# CH32H417QEU6-R0.net
KiCad netlist of a schematic drawn in Altium Designer
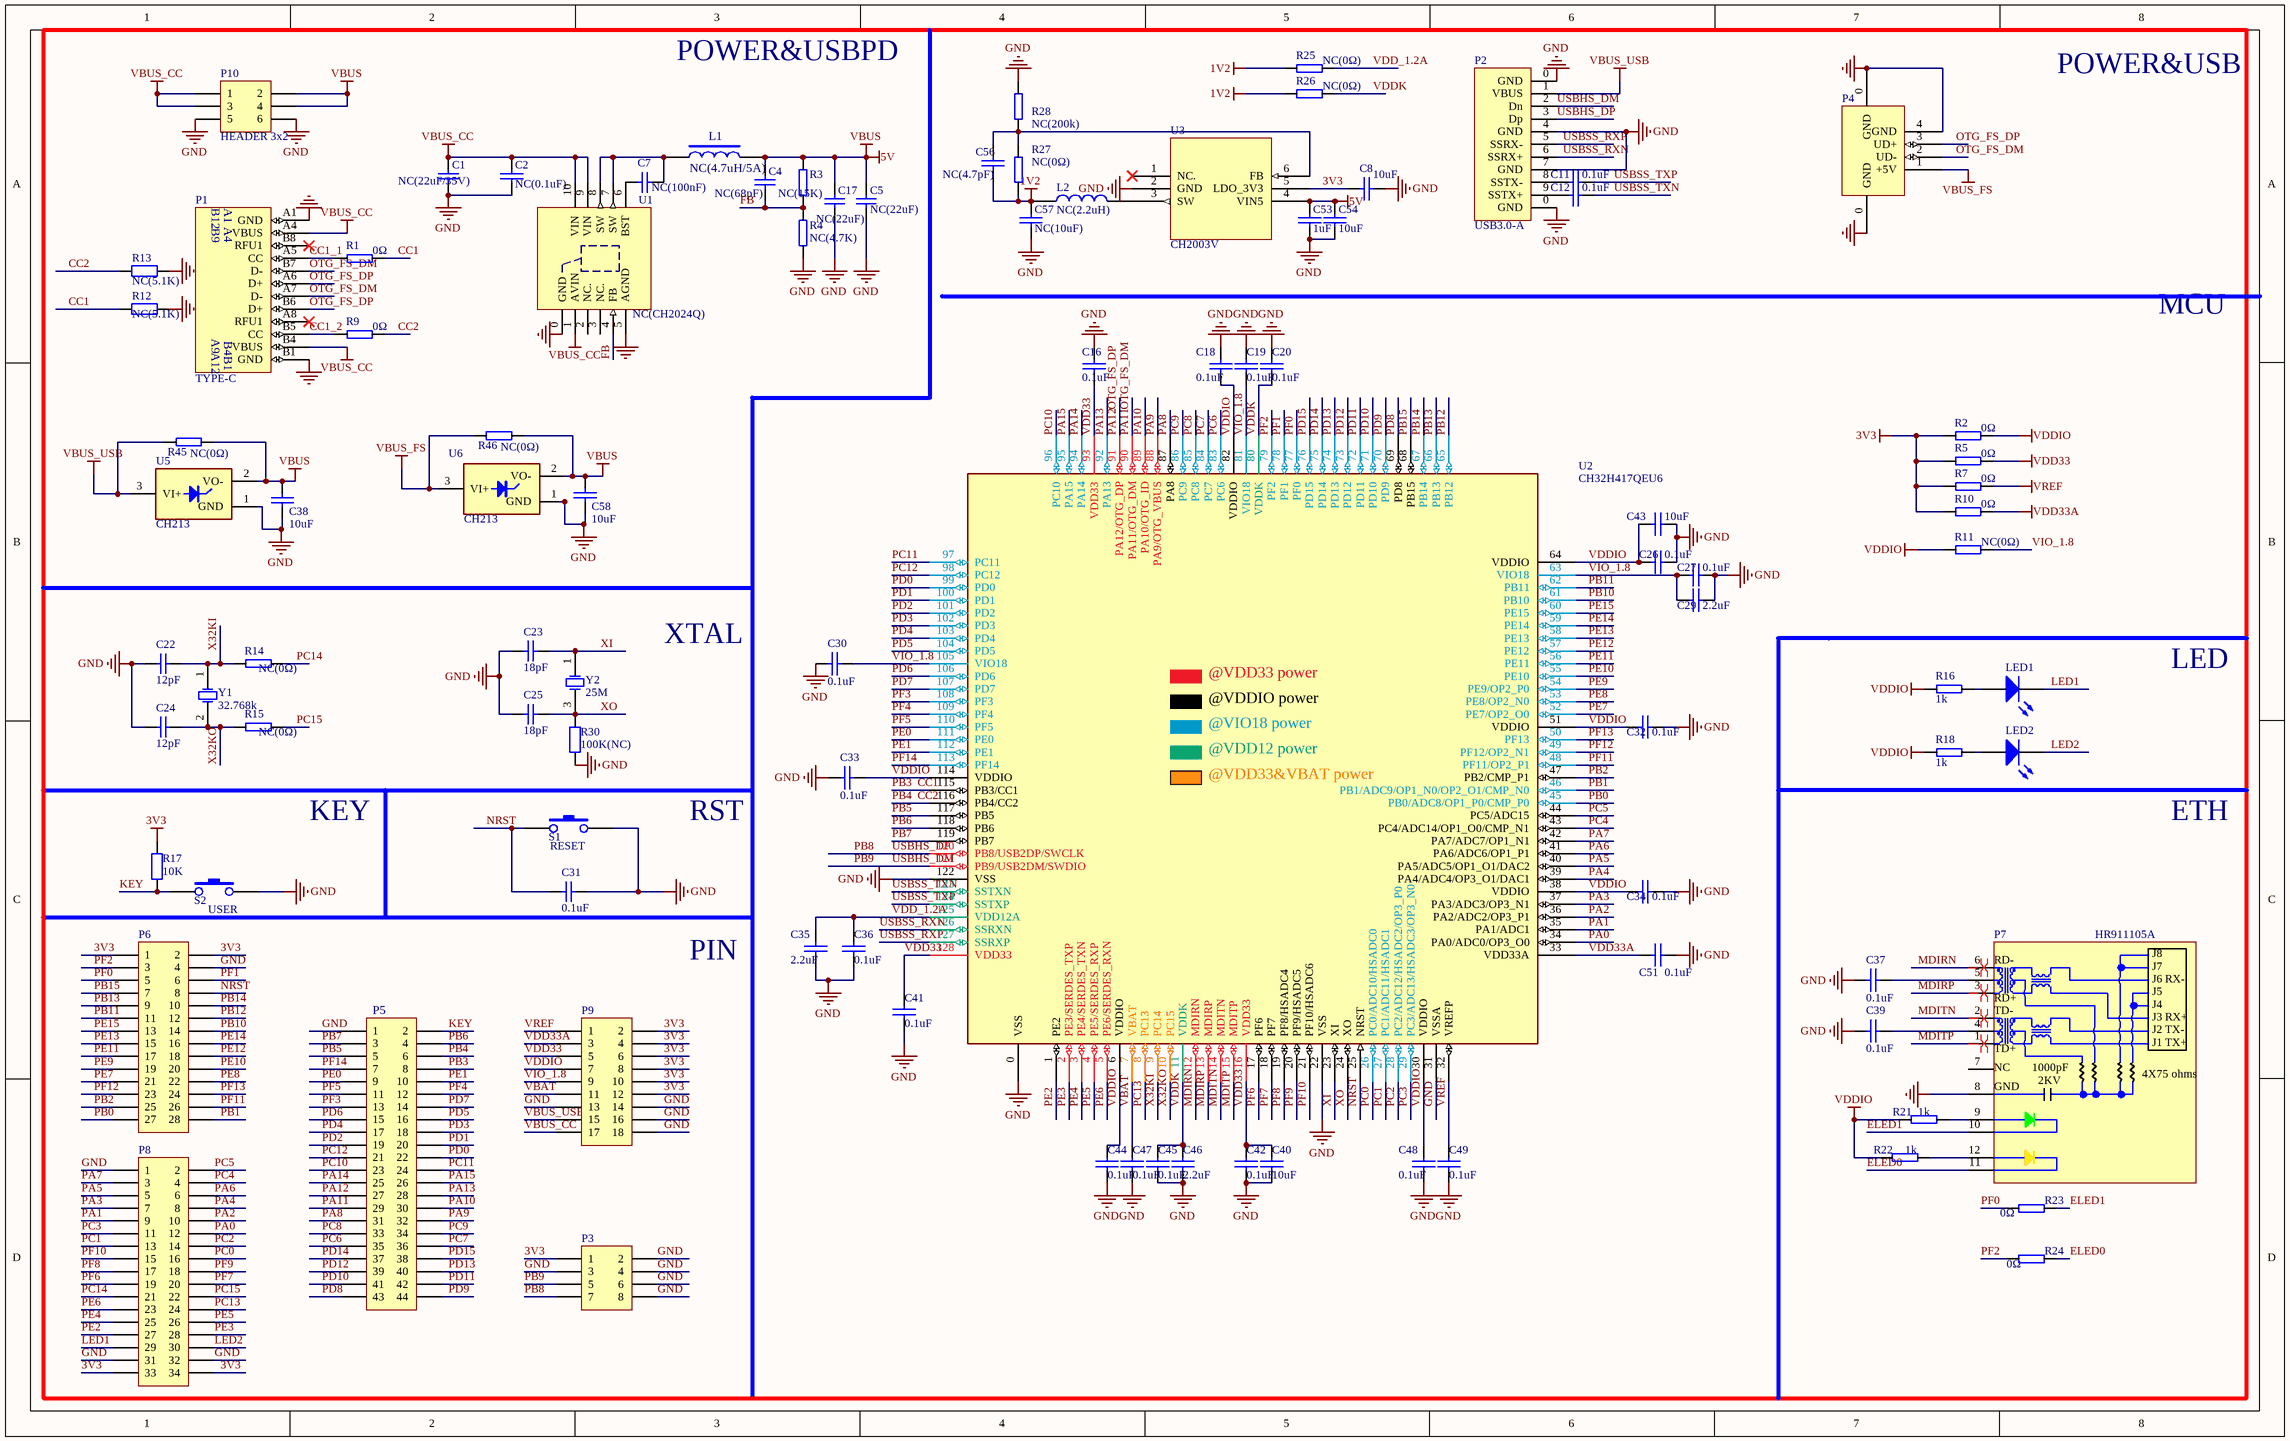
[diagram p0: CH32H417QEU6-R0.SchDoc]

(export (version "E")
  (design (tool "Eeschema 10.0.6"))
  (components
    (comp (ref "C1")
      (value "NC(22uF/35V)")
      (footprint "0805_C")
      (description "贴片电容")
      (libsource (lib "Miscellaneous Devices LC") (part "0603 100nF (104) 10% 50V"))
    )
    (comp (ref "C2")
      (value "NC(0.1uF)")
      (footprint "0402_C")
      (description "Capacitor")
      (libsource (lib "*") (part "CAP"))
    )
    (comp (ref "C4")
      (value "NC(68pF)")
      (footprint "0402_C")
      (description "贴片电容")
      (libsource (lib "Miscellaneous Devices LC") (part "0603 100nF (104) 10% 50V"))
    )
    (comp (ref "C5")
      (value "NC(22uF)")
      (footprint "0805_C")
      (description "贴片电容")
      (libsource (lib "Miscellaneous Devices LC") (part "0603 100nF (104) 10% 50V"))
    )
    (comp (ref "C7")
      (value "NC(100nF)")
      (footprint "0402_C")
      (description "贴片电容")
      (libsource (lib "Miscellaneous Devices LC") (part "0603 1uF (105) 10% 50V"))
    )
    (comp (ref "C8")
      (value "10uF")
      (footprint "0603_C")
      (description "Capacitor")
      (libsource (lib "*") (part "CAP"))
    )
    (comp (ref "C11")
      (value "0.1uF")
      (footprint "0402_C")
      (description "Capacitor")
      (libsource (lib "*") (part "CAP"))
    )
    (comp (ref "C12")
      (value "0.1uF")
      (footprint "0402_C")
      (description "Capacitor")
      (libsource (lib "*") (part "CAP"))
    )
    (comp (ref "C16")
      (value "0.1uF")
      (footprint "0402_C")
      (description "Capacitor")
      (libsource (lib "*") (part "CAP"))
    )
    (comp (ref "C17")
      (value "NC(22uF)")
      (footprint "0805_C")
      (description "贴片电容")
      (libsource (lib "Miscellaneous Devices LC") (part "0603 100nF (104) 10% 50V"))
    )
    (comp (ref "C18")
      (value "0.1uF")
      (footprint "0402_C")
      (description "Capacitor")
      (libsource (lib "*") (part "CAP"))
    )
    (comp (ref "C19")
      (value "0.1uF")
      (footprint "0402_C")
      (description "Capacitor")
      (libsource (lib "*") (part "CAP"))
    )
    (comp (ref "C20")
      (value "0.1uF")
      (footprint "0402_C")
      (description "Capacitor")
      (libsource (lib "*") (part "CAP"))
    )
    (comp (ref "C22")
      (value "12pF")
      (footprint "0402_C")
      (description "Capacitor")
      (libsource (lib "Miscellaneous Devices") (part "Cap"))
    )
    (comp (ref "C23")
      (value "18pF")
      (footprint "0402_C")
      (description "Capacitor")
      (libsource (lib "Miscellaneous Devices") (part "Cap"))
    )
    (comp (ref "C24")
      (value "12pF")
      (footprint "0402_C")
      (description "Capacitor")
      (libsource (lib "Miscellaneous Devices") (part "Cap"))
    )
    (comp (ref "C25")
      (value "18pF")
      (footprint "0402_C")
      (description "Capacitor")
      (libsource (lib "Miscellaneous Devices") (part "Cap"))
    )
    (comp (ref "C26")
      (value "0.1uF")
      (footprint "0402_C")
      (description "Capacitor")
      (libsource (lib "*") (part "CAP"))
    )
    (comp (ref "C27")
      (value "0.1uF")
      (footprint "0402_C")
      (description "Capacitor")
      (libsource (lib "*") (part "CAP"))
    )
    (comp (ref "C29")
      (value "2.2uF")
      (footprint "0402_C")
      (description "Capacitor")
      (libsource (lib "*") (part "CAP"))
    )
    (comp (ref "C30")
      (value "0.1uF")
      (footprint "0402_C")
      (description "Capacitor")
      (libsource (lib "*") (part "CAP"))
    )
    (comp (ref "C31")
      (value "0.1uF")
      (footprint "0402_C")
      (description "Capacitor")
      (libsource (lib "Miscellaneous Devices") (part "Cap"))
    )
    (comp (ref "C32")
      (value "0.1uF")
      (footprint "0402_C")
      (description "Capacitor")
      (libsource (lib "*") (part "CAP"))
    )
    (comp (ref "C33")
      (value "0.1uF")
      (footprint "0402_C")
      (description "Capacitor")
      (libsource (lib "*") (part "CAP"))
    )
    (comp (ref "C34")
      (value "0.1uF")
      (footprint "0402_C")
      (description "Capacitor")
      (libsource (lib "*") (part "CAP"))
    )
    (comp (ref "C35")
      (value "2.2uF")
      (footprint "0402_C")
      (description "Capacitor")
      (libsource (lib "*") (part "CAP"))
    )
    (comp (ref "C36")
      (value "0.1uF")
      (footprint "0402_C")
      (description "Capacitor")
      (libsource (lib "*") (part "CAP"))
    )
    (comp (ref "C37")
      (value "0.1uF")
      (footprint "0402_C")
      (description "Capacitor")
      (libsource (lib "wch_sch_others") (part "CAP"))
    )
    (comp (ref "C38")
      (value "10uF")
      (footprint "0603_C")
      (description "Capacitor")
      (libsource (lib "") (part "CAP_1"))
    )
    (comp (ref "C39")
      (value "0.1uF")
      (footprint "0402_C")
      (description "Capacitor")
      (libsource (lib "wch_sch_others") (part "CAP"))
    )
    (comp (ref "C40")
      (value "10uF")
      (footprint "0603_C")
      (description "Capacitor")
      (libsource (lib "*") (part "CAP"))
    )
    (comp (ref "C41")
      (value "0.1uF")
      (footprint "0402_C")
      (description "Capacitor")
      (libsource (lib "*") (part "CAP"))
    )
    (comp (ref "C42")
      (value "0.1uF")
      (footprint "0402_C")
      (description "Capacitor")
      (libsource (lib "*") (part "CAP"))
    )
    (comp (ref "C43")
      (value "10uF")
      (footprint "0603_C")
      (description "Capacitor")
      (libsource (lib "*") (part "CAP"))
    )
    (comp (ref "C44")
      (value "0.1uF")
      (footprint "0402_C")
      (description "Capacitor")
      (libsource (lib "*") (part "CAP"))
    )
    (comp (ref "C45")
      (value "0.1uF")
      (footprint "0402_C")
      (description "Capacitor")
      (libsource (lib "*") (part "CAP"))
    )
    (comp (ref "C46")
      (value "2.2uF")
      (footprint "0402_C")
      (description "Capacitor")
      (libsource (lib "*") (part "CAP"))
    )
    (comp (ref "C47")
      (value "0.1uF")
      (footprint "0402_C")
      (description "Capacitor")
      (libsource (lib "*") (part "CAP"))
    )
    (comp (ref "C48")
      (value "0.1uF")
      (footprint "0402_C")
      (description "Capacitor")
      (libsource (lib "*") (part "CAP"))
    )
    (comp (ref "C49")
      (value "0.1uF")
      (footprint "0402_C")
      (description "Capacitor")
      (libsource (lib "*") (part "CAP"))
    )
    (comp (ref "C51")
      (value "0.1uF")
      (footprint "0402_C")
      (description "Capacitor")
      (libsource (lib "*") (part "CAP"))
    )
    (comp (ref "C53")
      (value "1uF")
      (footprint "0402_C")
      (description "Capacitor")
      (libsource (lib "") (part "CAP_2"))
    )
    (comp (ref "C54")
      (value "10uF")
      (footprint "0603_C")
      (description "Capacitor")
      (libsource (lib "*") (part "CAP"))
    )
    (comp (ref "C56")
      (value "NC(4.7pF)")
      (footprint "0402_C")
      (description "Capacitor")
      (libsource (lib "") (part "CAP_2"))
    )
    (comp (ref "C57")
      (value "NC(10uF)")
      (footprint "0603_C")
      (description "Capacitor")
      (libsource (lib "*") (part "CAP"))
    )
    (comp (ref "C58")
      (value "10uF")
      (footprint "0603_C")
      (description "Capacitor")
      (libsource (lib "") (part "CAP_1"))
    )
    (comp (ref "L1")
      (value "NC(4.7uH/5A)")
      (footprint "IND-SMD_L7.0-W6.6")
      (libsource (lib "wch_sch_others") (part "INDUCTOR"))
    )
    (comp (ref "L2") (value "NC(2.2uH)") (footprint "CD32") (libsource (lib "*") (part "INDUCTOR")))
    (comp (ref "LED1")
      (value "LED2  blue")
      (footprint "0603+")
      (description "Typical INFRARED GaAs LED")
      (fields (field (name "PUBLISHER") "Altium Limited"))
      (libsource (lib "Miscellaneous Devices") (part "LED0"))
    )
    (comp (ref "LED2")
      (value "LED1   blue")
      (footprint "0603+")
      (description "Typical INFRARED GaAs LED")
      (fields (field (name "PUBLISHER") "Altium Limited"))
      (libsource (lib "Miscellaneous Devices") (part "LED0"))
    )
    (comp (ref "P1")
      (value "TYPE-C")
      (footprint "TYPE-C-Receptacle-2.0")
      (libsource (lib "*") (part "TYPE-C1"))
    )
    (comp (ref "P2")
      (value "USB3.0-A")
      (footprint "USB3.0-A-Receptacle")
      (libsource (lib "wch_sch_others") (part "USB3.0-A"))
    )
    (comp (ref "P3")
      (value "HEADER 4x2")
      (footprint "MYPCB:IDC8-2.54mm")
      (description "Header, 4-Pin, Dual row")
      (libsource (lib "wch_sch_others") (part "HEADER 4x2"))
    )
    (comp (ref "P4")
      (value "USB_A")
      (footprint "USBAF")
      (description "USB Port")
      (libsource (lib "*") (part "USB"))
    )
    (comp (ref "P5")
      (value "~")
      (footprint "MYPCB:IDC44-2.54MM")
      (description "Header, 22-Pin, Dual row")
      (libsource (lib "wch_sch_others") (part "HEADER 22x2"))
    )
    (comp (ref "P6")
      (value "HEADER 14x2")
      (footprint "MYPCB:IDC28-2.54MM")
      (description "Header, 14-Pin, Dual row")
      (libsource (lib "wch_sch_others") (part "HEADER 14x2"))
    )
    (comp (ref "P7") (value "HR911105A") (footprint "HR911105A") (libsource (lib "*") (part "HR911105A")))
    (comp (ref "P8")
      (value "HEADER 17x2")
      (footprint "MYPCB:IDC34-2.54MM")
      (description "Header, 17-Pin, Dual row")
      (libsource (lib "wch_sch_others") (part "HEADER 17x2"))
    )
    (comp (ref "P9")
      (value "HEADER 9x2")
      (footprint "MYPCB:IDC18-2.54MM")
      (description "Header, 9-Pin, Dual row")
      (libsource (lib "wch_sch_others") (part "HEADER 9x2"))
    )
    (comp (ref "P10")
      (value "HEADER 3x2")
      (footprint "MYPCB:IDC6-2.54mm")
      (description "Header, 3-Pin, Dual row")
      (libsource (lib "wch_sch_others") (part "HEADER 3x2"))
    )
    (comp (ref "R1") (value "0Ω") (footprint "0402") (libsource (lib "wch_sch_others") (part "RES")))
    (comp (ref "R2") (value "0Ω") (footprint "0402") (libsource (lib "wch_sch_others") (part "RES")))
    (comp (ref "R3") (value "NC(15K)") (footprint "0402") (libsource (lib "wch_sch_others(1)") (part "RES")))
    (comp (ref "R4") (value "NC(4.7K)") (footprint "0402") (libsource (lib "wch_sch_others(1)") (part "RES")))
    (comp (ref "R5") (value "0Ω") (footprint "0402") (libsource (lib "wch_sch_others") (part "RES")))
    (comp (ref "R7") (value "0Ω") (footprint "0402") (libsource (lib "wch_sch_others") (part "RES")))
    (comp (ref "R9") (value "0Ω") (footprint "0402") (libsource (lib "wch_sch_others") (part "RES")))
    (comp (ref "R10") (value "0Ω") (footprint "0402") (libsource (lib "wch_sch_others") (part "RES")))
    (comp (ref "R11") (value "NC(0Ω)") (footprint "0402") (libsource (lib "wch_sch_others") (part "RES")))
    (comp (ref "R12")
      (value "NC(5.1K)")
      (footprint "0402")
      (description "Resistor")
      (libsource (lib "Miscellaneous Devices") (part "Res2"))
    )
    (comp (ref "R13")
      (value "NC(5.1K)")
      (footprint "0402")
      (description "Resistor")
      (libsource (lib "Miscellaneous Devices") (part "Res2"))
    )
    (comp (ref "R14") (value "NC(0Ω)") (footprint "0402") (libsource (lib "wch_sch_others") (part "RES")))
    (comp (ref "R15") (value "NC(0Ω)") (footprint "0402") (libsource (lib "wch_sch_others") (part "RES")))
    (comp (ref "R16") (value "1k") (footprint "0402") (libsource (lib "wch_sch_others") (part "RES")))
    (comp (ref "R17")
      (value "10K")
      (footprint "0402")
      (description "Resistor")
      (libsource (lib "") (part "Res2_1"))
    )
    (comp (ref "R18") (value "1k") (footprint "0402") (libsource (lib "wch_sch_others") (part "RES")))
    (comp (ref "R21") (value "1k") (footprint "0402") (libsource (lib "") (part "RES_1")))
    (comp (ref "R22") (value "1k") (footprint "0402") (libsource (lib "") (part "RES_1")))
    (comp (ref "R23") (value "0Ω") (footprint "0402") (libsource (lib "") (part "RES_1")))
    (comp (ref "R24") (value "0Ω") (footprint "0402") (libsource (lib "") (part "RES_1")))
    (comp (ref "R25") (value "NC(0Ω)") (footprint "0402") (libsource (lib "wch_sch_others") (part "RES")))
    (comp (ref "R26") (value "NC(0Ω)") (footprint "0402") (libsource (lib "wch_sch_others") (part "RES")))
    (comp (ref "R27") (value "NC(0Ω)") (footprint "0402") (libsource (lib "wch_sch_others") (part "RES")))
    (comp (ref "R28") (value "NC(200k)") (footprint "0402") (libsource (lib "wch_sch_others") (part "RES")))
    (comp (ref "R30")
      (value "100K(NC)")
      (footprint "0402")
      (description "Resistor")
      (libsource (lib "") (part "Res2_2"))
    )
    (comp (ref "R45") (value "NC(0Ω)") (footprint "0402") (libsource (lib "") (part "RES_1")))
    (comp (ref "R46") (value "NC(0Ω)") (footprint "0402") (libsource (lib "") (part "RES_1")))
    (comp (ref "S1")
      (value "RESET")
      (footprint "SMD_6.1x3.65x2.5mm-KEY")
      (libsource (lib "wch_sch_others") (part "KEY1"))
    )
    (comp (ref "S2")
      (value "USER")
      (footprint "SMD_6.1x3.65x2.5mm-KEY")
      (libsource (lib "wch_sch_others") (part "KEY1"))
    )
    (comp (ref "U1")
      (value "NC(CH2024Q)")
      (footprint "DFN10_3X3")
      (description "Step-Down DC-DC Converter, 28V input, FB 1.2V, 3A output")
      (libsource (lib "DHXXXSCH") (part "CH2024Q"))
    )
    (comp (ref "U2")
      (value "CH32H417QEU6")
      (footprint "QFN128_12.3X12.3")
      (description "RISC-V FPU HD-MCU, 384MHz, USB3.0 & PD, 100M Ethernet, DVP, SDMMC, QSPI, OPA, ADC, DAC")
      (libsource (lib "DHXXXSCH") (part "CH32H417QET6"))
    )
    (comp (ref "U3")
      (value "CH2003V")
      (footprint "SOT-23-6")
      (description "Step-Down DC-DC Converter, 5V input, FB 0.6V, 800mA output, with LDO 3.3V * 200mA")
      (libsource (lib "DHXXXSCH") (part "CH2003K"))
    )
    (comp (ref "U5")
      (value "CH213")
      (footprint "SOT-23-3")
      (description "Ideal Diode 5V*1A")
      (libsource (lib "CHXXX") (part "CH213E"))
    )
    (comp (ref "U6")
      (value "CH213")
      (footprint "SOT-23-3")
      (description "Ideal Diode 5V*1A")
      (libsource (lib "CHXXX") (part "CH213E"))
    )
    (comp (ref "Y1")
      (value "32.768k")
      (footprint "FC-135")
      (description "Crystal Oscillator")
      (fields (field (name "PUBLISHER") "Altium Limited"))
      (libsource (lib "") (part "XTAL_1"))
    )
    (comp (ref "Y2")
      (value "25M")
      (footprint "XT3225")
      (description "Crystal Oscillator")
      (fields (field (name "PUBLISHER") "Altium Limited"))
      (libsource (lib "Miscellaneous Devices") (part "XTAL"))
    )
  )
  (nets
    (net (code "2") (name "/CC1") (class "Default")
      (node (ref "P5") (pin "8") (pinfunction "8_8") (pintype "passive"))
      (node (ref "R1") (pin "1") (pintype "passive"))
      (node (ref "R12") (pin "1") (pinfunction "1_1") (pintype "passive"))
      (node (ref "U2") (pin "115") (pinfunction "PB3/CC1_115") (pintype "bidirectional"))
    )
    (net (code "3") (name "/CC1_1") (class "Default")
      (node (ref "P1") (pin "A5") (pinfunction "CC_A5") (pintype "bidirectional"))
      (node (ref "R1") (pin "2") (pintype "passive"))
    )
    (net (code "4") (name "/CC1_2") (class "Default")
      (node (ref "P1") (pin "B5") (pinfunction "CC_B5") (pintype "bidirectional"))
      (node (ref "R9") (pin "2") (pintype "passive"))
    )
    (net (code "5") (name "/CC2") (class "Default")
      (node (ref "P5") (pin "6") (pinfunction "6_6") (pintype "passive"))
      (node (ref "R13") (pin "1") (pinfunction "1_1") (pintype "passive"))
      (node (ref "R9") (pin "1") (pintype "passive"))
      (node (ref "U2") (pin "116") (pinfunction "PB4/CC2_116") (pintype "bidirectional"))
    )
    (net (code "6") (name "/ELED0") (class "Default")
      (node (ref "P7") (pin "11") (pintype "passive"))
      (node (ref "R24") (pin "2") (pintype "passive"))
    )
    (net (code "7") (name "/ELED1") (class "Default")
      (node (ref "P7") (pin "10") (pintype "passive"))
      (node (ref "R23") (pin "2") (pintype "passive"))
    )
    (net (code "8") (name "/FB") (class "Default")
      (node (ref "C4") (pin "2") (pinfunction "2_2") (pintype "passive"))
      (node (ref "R3") (pin "1") (pintype "passive"))
      (node (ref "R4") (pin "2") (pintype "passive"))
      (node (ref "U1") (pin "4") (pinfunction "FB_4") (pintype "input"))
    )
    (net (code "9") (name "/KEY") (class "Default")
      (node (ref "P5") (pin "2") (pinfunction "2_2") (pintype "passive"))
      (node (ref "R17") (pin "2") (pinfunction "2_2") (pintype "passive"))
      (node (ref "S2") (pin "1") (pinfunction "1_1") (pintype "passive"))
    )
    (net (code "10") (name "/LED1") (class "Default")
      (node (ref "LED1") (pin "2") (pinfunction "K_2") (pintype "passive"))
      (node (ref "P8") (pin "29") (pinfunction "29_29") (pintype "passive"))
    )
    (net (code "11") (name "/LED2") (class "Default")
      (node (ref "LED2") (pin "2") (pinfunction "K_2") (pintype "passive"))
      (node (ref "P8") (pin "30") (pinfunction "30_30") (pintype "passive"))
    )
    (net (code "12") (name "/MDIRN") (class "Default")
      (node (ref "P7") (pin "6") (pintype "passive"))
      (node (ref "U2") (pin "12") (pinfunction "MDIRN_12") (pintype "bidirectional"))
    )
    (net (code "13") (name "/MDIRP") (class "Default")
      (node (ref "P7") (pin "3") (pintype "passive"))
      (node (ref "U2") (pin "13") (pinfunction "MDIRP_13") (pintype "bidirectional"))
    )
    (net (code "14") (name "/MDITN") (class "Default")
      (node (ref "P7") (pin "2") (pintype "passive"))
      (node (ref "U2") (pin "14") (pinfunction "MDITN_14") (pintype "bidirectional"))
    )
    (net (code "15") (name "/MDITP") (class "Default")
      (node (ref "P7") (pin "1") (pintype "passive"))
      (node (ref "U2") (pin "15") (pinfunction "MDITP_15") (pintype "bidirectional"))
    )
    (net (code "16") (name "/NRST") (class "Default")
      (node (ref "C31") (pin "2") (pinfunction "2_2") (pintype "passive"))
      (node (ref "P6") (pin "8") (pinfunction "8_8") (pintype "passive"))
      (node (ref "S1") (pin "1") (pinfunction "1_1") (pintype "passive"))
      (node (ref "U2") (pin "25") (pinfunction "NRST_25") (pintype "input"))
    )
    (net (code "17") (name "/OTG_FS_DM") (class "Default")
      (node (ref "P1") (pin "A7") (pinfunction "D-_A7") (pintype "bidirectional"))
      (node (ref "P1") (pin "B7") (pinfunction "D-_B7") (pintype "bidirectional"))
      (node (ref "P4") (pin "2") (pinfunction "UD-_2") (pintype "bidirectional"))
      (node (ref "P5") (pin "29") (pinfunction "29_29") (pintype "passive"))
      (node (ref "U2") (pin "90") (pinfunction "PA11/OTG_DM_90") (pintype "bidirectional"))
    )
    (net (code "18") (name "/OTG_FS_DP") (class "Default")
      (node (ref "P1") (pin "A6") (pinfunction "D+_A6") (pintype "bidirectional"))
      (node (ref "P1") (pin "B6") (pinfunction "D+_B6") (pintype "bidirectional"))
      (node (ref "P4") (pin "3") (pinfunction "UD+_3") (pintype "bidirectional"))
      (node (ref "P5") (pin "27") (pinfunction "27_27") (pintype "passive"))
      (node (ref "U2") (pin "91") (pinfunction "PA12/OTG_DP_91") (pintype "bidirectional"))
    )
    (net (code "19") (name "/PA0") (class "Default")
      (node (ref "P8") (pin "12") (pinfunction "12_12") (pintype "passive"))
      (node (ref "U2") (pin "34") (pinfunction "PA0/ADC0/OP3_O0_34") (pintype "bidirectional"))
    )
    (net (code "20") (name "/PA1") (class "Default")
      (node (ref "P8") (pin "9") (pinfunction "9_9") (pintype "passive"))
      (node (ref "U2") (pin "35") (pinfunction "PA1/ADC1_35") (pintype "bidirectional"))
    )
    (net (code "21") (name "/PA2") (class "Default")
      (node (ref "P8") (pin "10") (pinfunction "10_10") (pintype "passive"))
      (node (ref "U2") (pin "36") (pinfunction "PA2/ADC2/OP3_P1_36") (pintype "bidirectional"))
    )
    (net (code "22") (name "/PA3") (class "Default")
      (node (ref "P8") (pin "7") (pinfunction "7_7") (pintype "passive"))
      (node (ref "U2") (pin "37") (pinfunction "PA3/ADC3/OP3_N1_37") (pintype "bidirectional"))
    )
    (net (code "23") (name "/PA4") (class "Default")
      (node (ref "P8") (pin "8") (pinfunction "8_8") (pintype "passive"))
      (node (ref "U2") (pin "39") (pinfunction "PA4/ADC4/OP3_O1/DAC1_39") (pintype "bidirectional"))
    )
    (net (code "24") (name "/PA5") (class "Default")
      (node (ref "P8") (pin "5") (pinfunction "5_5") (pintype "passive"))
      (node (ref "U2") (pin "40") (pinfunction "PA5/ADC5/OP1_O1/DAC2_40") (pintype "bidirectional"))
    )
    (net (code "25") (name "/PA6") (class "Default")
      (node (ref "P8") (pin "6") (pinfunction "6_6") (pintype "passive"))
      (node (ref "U2") (pin "41") (pinfunction "PA6/ADC6/OP1_P1_41") (pintype "bidirectional"))
    )
    (net (code "26") (name "/PA7") (class "Default")
      (node (ref "P8") (pin "3") (pinfunction "3_3") (pintype "passive"))
      (node (ref "U2") (pin "42") (pinfunction "PA7/ADC7/OP1_N1_42") (pintype "bidirectional"))
    )
    (net (code "27") (name "/PA8") (class "Default")
      (node (ref "P5") (pin "31") (pinfunction "31_31") (pintype "passive"))
      (node (ref "U2") (pin "87") (pinfunction "PA8_87") (pintype "bidirectional"))
    )
    (net (code "28") (name "/PA9") (class "Default")
      (node (ref "P5") (pin "32") (pinfunction "32_32") (pintype "passive"))
      (node (ref "U2") (pin "88") (pinfunction "PA9/OTG_VBUS_88") (pintype "bidirectional"))
    )
    (net (code "29") (name "/PA10") (class "Default")
      (node (ref "P5") (pin "30") (pinfunction "30_30") (pintype "passive"))
      (node (ref "U2") (pin "89") (pinfunction "PA10/OTG_ID_89") (pintype "bidirectional"))
    )
    (net (code "30") (name "/PA13") (class "Default")
      (node (ref "P5") (pin "28") (pinfunction "28_28") (pintype "passive"))
      (node (ref "U2") (pin "92") (pinfunction "PA13_92") (pintype "bidirectional"))
    )
    (net (code "31") (name "/PA14") (class "Default")
      (node (ref "P5") (pin "25") (pinfunction "25_25") (pintype "passive"))
      (node (ref "U2") (pin "94") (pinfunction "PA14_94") (pintype "bidirectional"))
    )
    (net (code "32") (name "/PA15") (class "Default")
      (node (ref "P5") (pin "26") (pinfunction "26_26") (pintype "passive"))
      (node (ref "U2") (pin "95") (pinfunction "PA15_95") (pintype "bidirectional"))
    )
    (net (code "33") (name "/PB0") (class "Default")
      (node (ref "P6") (pin "27") (pinfunction "27_27") (pintype "passive"))
      (node (ref "U2") (pin "45") (pinfunction "PB0/ADC8/OP1_P0/CMP_P0_45") (pintype "bidirectional"))
    )
    (net (code "34") (name "/PB1") (class "Default")
      (node (ref "P6") (pin "28") (pinfunction "28_28") (pintype "passive"))
      (node (ref "U2") (pin "46") (pinfunction "PB1/ADC9/OP1_N0/OP2_O1/CMP_N0_46") (pintype "bidirectional"))
    )
    (net (code "35") (name "/PB2") (class "Default")
      (node (ref "P6") (pin "25") (pinfunction "25_25") (pintype "passive"))
      (node (ref "U2") (pin "47") (pinfunction "PB2/CMP_P1_47") (pintype "bidirectional"))
    )
    (net (code "36") (name "/PB5") (class "Default")
      (node (ref "P5") (pin "5") (pinfunction "5_5") (pintype "passive"))
      (node (ref "U2") (pin "117") (pinfunction "PB5_117") (pintype "bidirectional"))
    )
    (net (code "37") (name "/PB6") (class "Default")
      (node (ref "P5") (pin "4") (pinfunction "4_4") (pintype "passive"))
      (node (ref "U2") (pin "118") (pinfunction "PB6_118") (pintype "bidirectional"))
    )
    (net (code "38") (name "/PB7") (class "Default")
      (node (ref "P5") (pin "3") (pinfunction "3_3") (pintype "passive"))
      (node (ref "U2") (pin "119") (pinfunction "PB7_119") (pintype "bidirectional"))
    )
    (net (code "39") (name "/PB8") (class "Default")
      (node (ref "P2") (pin "3") (pinfunction "Dp_3") (pintype "passive"))
      (node (ref "P3") (pin "7") (pinfunction "7_7") (pintype "passive"))
      (node (ref "U2") (pin "120") (pinfunction "PB8/USB2DP/SWCLK_120") (pintype "bidirectional"))
    )
    (net (code "40") (name "/PB9") (class "Default")
      (node (ref "P2") (pin "2") (pinfunction "Dn_2") (pintype "passive"))
      (node (ref "P3") (pin "5") (pinfunction "5_5") (pintype "passive"))
      (node (ref "U2") (pin "121") (pinfunction "PB9/USB2DM/SWDIO_121") (pintype "bidirectional"))
    )
    (net (code "41") (name "/PB10") (class "Default")
      (node (ref "P6") (pin "14") (pinfunction "14_14") (pintype "passive"))
      (node (ref "U2") (pin "61") (pinfunction "PB10_61") (pintype "bidirectional"))
    )
    (net (code "42") (name "/PB11") (class "Default")
      (node (ref "P6") (pin "11") (pinfunction "11_11") (pintype "passive"))
      (node (ref "U2") (pin "62") (pinfunction "PB11_62") (pintype "bidirectional"))
    )
    (net (code "43") (name "/PB12") (class "Default")
      (node (ref "P6") (pin "12") (pinfunction "12_12") (pintype "passive"))
      (node (ref "U2") (pin "65") (pinfunction "PB12_65") (pintype "bidirectional"))
    )
    (net (code "44") (name "/PB13") (class "Default")
      (node (ref "P6") (pin "9") (pinfunction "9_9") (pintype "passive"))
      (node (ref "U2") (pin "66") (pinfunction "PB13_66") (pintype "bidirectional"))
    )
    (net (code "45") (name "/PB14") (class "Default")
      (node (ref "P6") (pin "10") (pinfunction "10_10") (pintype "passive"))
      (node (ref "U2") (pin "67") (pinfunction "PB14_67") (pintype "bidirectional"))
    )
    (net (code "46") (name "/PB15") (class "Default")
      (node (ref "P6") (pin "7") (pinfunction "7_7") (pintype "passive"))
      (node (ref "U2") (pin "68") (pinfunction "PB15_68") (pintype "bidirectional"))
    )
    (net (code "47") (name "/PC0") (class "Default")
      (node (ref "P8") (pin "16") (pinfunction "16_16") (pintype "passive"))
      (node (ref "U2") (pin "26") (pinfunction "PC0/ADC10/HSADC0_26") (pintype "bidirectional"))
    )
    (net (code "48") (name "/PC1") (class "Default")
      (node (ref "P8") (pin "13") (pinfunction "13_13") (pintype "passive"))
      (node (ref "U2") (pin "27") (pinfunction "PC1/ADC11/HSADC1_27") (pintype "bidirectional"))
    )
    (net (code "49") (name "/PC2") (class "Default")
      (node (ref "P8") (pin "14") (pinfunction "14_14") (pintype "passive"))
      (node (ref "U2") (pin "28") (pinfunction "PC2/ADC12/HSADC2/OP3_P0_28") (pintype "bidirectional"))
    )
    (net (code "50") (name "/PC3") (class "Default")
      (node (ref "P8") (pin "11") (pinfunction "11_11") (pintype "passive"))
      (node (ref "U2") (pin "29") (pinfunction "PC3/ADC13/HSADC3/OP3_N0_29") (pintype "bidirectional"))
    )
    (net (code "51") (name "/PC4") (class "Default")
      (node (ref "P8") (pin "4") (pinfunction "4_4") (pintype "passive"))
      (node (ref "U2") (pin "43") (pinfunction "PC4/ADC14/OP1_O0/CMP_N1_43") (pintype "bidirectional"))
    )
    (net (code "52") (name "/PC5") (class "Default")
      (node (ref "P8") (pin "2") (pinfunction "2_2") (pintype "passive"))
      (node (ref "U2") (pin "44") (pinfunction "PC5/ADC15_44") (pintype "bidirectional"))
    )
    (net (code "53") (name "/PC6") (class "Default")
      (node (ref "P5") (pin "35") (pinfunction "35_35") (pintype "passive"))
      (node (ref "U2") (pin "83") (pinfunction "PC6_83") (pintype "bidirectional"))
    )
    (net (code "54") (name "/PC7") (class "Default")
      (node (ref "P5") (pin "36") (pinfunction "36_36") (pintype "passive"))
      (node (ref "U2") (pin "84") (pinfunction "PC7_84") (pintype "bidirectional"))
    )
    (net (code "55") (name "/PC8") (class "Default")
      (node (ref "P5") (pin "33") (pinfunction "33_33") (pintype "passive"))
      (node (ref "U2") (pin "85") (pinfunction "PC8_85") (pintype "bidirectional"))
    )
    (net (code "56") (name "/PC9") (class "Default")
      (node (ref "P5") (pin "34") (pinfunction "34_34") (pintype "passive"))
      (node (ref "U2") (pin "86") (pinfunction "PC9_86") (pintype "bidirectional"))
    )
    (net (code "57") (name "/PC10") (class "Default")
      (node (ref "P5") (pin "23") (pinfunction "23_23") (pintype "passive"))
      (node (ref "U2") (pin "96") (pinfunction "PC10_96") (pintype "bidirectional"))
    )
    (net (code "58") (name "/PC11") (class "Default")
      (node (ref "P5") (pin "24") (pinfunction "24_24") (pintype "passive"))
      (node (ref "U2") (pin "97") (pinfunction "PC11_97") (pintype "bidirectional"))
    )
    (net (code "59") (name "/PC12") (class "Default")
      (node (ref "P5") (pin "21") (pinfunction "21_21") (pintype "passive"))
      (node (ref "U2") (pin "98") (pinfunction "PC12_98") (pintype "bidirectional"))
    )
    (net (code "60") (name "/PC13") (class "Default")
      (node (ref "P8") (pin "24") (pinfunction "24_24") (pintype "passive"))
      (node (ref "U2") (pin "8") (pinfunction "PC13_8") (pintype "bidirectional"))
    )
    (net (code "61") (name "/PC14") (class "Default")
      (node (ref "P8") (pin "21") (pinfunction "21_21") (pintype "passive"))
      (node (ref "R14") (pin "1") (pintype "passive"))
    )
    (net (code "62") (name "/PC15") (class "Default")
      (node (ref "P8") (pin "22") (pinfunction "22_22") (pintype "passive"))
      (node (ref "R15") (pin "1") (pintype "passive"))
    )
    (net (code "63") (name "/PD0") (class "Default")
      (node (ref "P5") (pin "22") (pinfunction "22_22") (pintype "passive"))
      (node (ref "U2") (pin "99") (pinfunction "PD0_99") (pintype "bidirectional"))
    )
    (net (code "64") (name "/PD1") (class "Default")
      (node (ref "P5") (pin "20") (pinfunction "20_20") (pintype "passive"))
      (node (ref "U2") (pin "100") (pinfunction "PD1_100") (pintype "bidirectional"))
    )
    (net (code "65") (name "/PD2") (class "Default")
      (node (ref "P5") (pin "19") (pinfunction "19_19") (pintype "passive"))
      (node (ref "U2") (pin "101") (pinfunction "PD2_101") (pintype "bidirectional"))
    )
    (net (code "66") (name "/PD3") (class "Default")
      (node (ref "P5") (pin "18") (pinfunction "18_18") (pintype "passive"))
      (node (ref "U2") (pin "102") (pinfunction "PD3_102") (pintype "bidirectional"))
    )
    (net (code "67") (name "/PD4") (class "Default")
      (node (ref "P5") (pin "17") (pinfunction "17_17") (pintype "passive"))
      (node (ref "U2") (pin "103") (pinfunction "PD4_103") (pintype "bidirectional"))
    )
    (net (code "68") (name "/PD5") (class "Default")
      (node (ref "P5") (pin "16") (pinfunction "16_16") (pintype "passive"))
      (node (ref "U2") (pin "104") (pinfunction "PD5_104") (pintype "bidirectional"))
    )
    (net (code "69") (name "/PD6") (class "Default")
      (node (ref "P5") (pin "15") (pinfunction "15_15") (pintype "passive"))
      (node (ref "U2") (pin "106") (pinfunction "PD6_106") (pintype "bidirectional"))
    )
    (net (code "70") (name "/PD7") (class "Default")
      (node (ref "P5") (pin "14") (pinfunction "14_14") (pintype "passive"))
      (node (ref "U2") (pin "107") (pinfunction "PD7_107") (pintype "bidirectional"))
    )
    (net (code "71") (name "/PD8") (class "Default")
      (node (ref "P5") (pin "43") (pinfunction "43_43") (pintype "passive"))
      (node (ref "U2") (pin "69") (pinfunction "PD8_69") (pintype "bidirectional"))
    )
    (net (code "72") (name "/PD9") (class "Default")
      (node (ref "P5") (pin "44") (pinfunction "44_44") (pintype "passive"))
      (node (ref "U2") (pin "70") (pinfunction "PD9_70") (pintype "bidirectional"))
    )
    (net (code "73") (name "/PD10") (class "Default")
      (node (ref "P5") (pin "41") (pinfunction "41_41") (pintype "passive"))
      (node (ref "U2") (pin "71") (pinfunction "PD10_71") (pintype "bidirectional"))
    )
    (net (code "74") (name "/PD11") (class "Default")
      (node (ref "P5") (pin "42") (pinfunction "42_42") (pintype "passive"))
      (node (ref "U2") (pin "72") (pinfunction "PD11_72") (pintype "bidirectional"))
    )
    (net (code "75") (name "/PD12") (class "Default")
      (node (ref "P5") (pin "39") (pinfunction "39_39") (pintype "passive"))
      (node (ref "U2") (pin "73") (pinfunction "PD12_73") (pintype "bidirectional"))
    )
    (net (code "76") (name "/PD13") (class "Default")
      (node (ref "P5") (pin "40") (pinfunction "40_40") (pintype "passive"))
      (node (ref "U2") (pin "74") (pinfunction "PD13_74") (pintype "bidirectional"))
    )
    (net (code "77") (name "/PD14") (class "Default")
      (node (ref "P5") (pin "37") (pinfunction "37_37") (pintype "passive"))
      (node (ref "U2") (pin "75") (pinfunction "PD14_75") (pintype "bidirectional"))
    )
    (net (code "78") (name "/PD15") (class "Default")
      (node (ref "P5") (pin "38") (pinfunction "38_38") (pintype "passive"))
      (node (ref "U2") (pin "76") (pinfunction "PD15_76") (pintype "bidirectional"))
    )
    (net (code "79") (name "/PE0") (class "Default")
      (node (ref "P5") (pin "9") (pinfunction "9_9") (pintype "passive"))
      (node (ref "U2") (pin "111") (pinfunction "PE0_111") (pintype "bidirectional"))
    )
    (net (code "80") (name "/PE1") (class "Default")
      (node (ref "P5") (pin "10") (pinfunction "10_10") (pintype "passive"))
      (node (ref "U2") (pin "112") (pinfunction "PE1_112") (pintype "bidirectional"))
    )
    (net (code "81") (name "/PE2") (class "Default")
      (node (ref "P8") (pin "27") (pinfunction "27_27") (pintype "passive"))
      (node (ref "U2") (pin "1") (pinfunction "PE2_1") (pintype "bidirectional"))
    )
    (net (code "82") (name "/PE3") (class "Default")
      (node (ref "P8") (pin "28") (pinfunction "28_28") (pintype "passive"))
      (node (ref "U2") (pin "2") (pinfunction "PE3/SERDES_TXP_2") (pintype "bidirectional"))
    )
    (net (code "83") (name "/PE4") (class "Default")
      (node (ref "P8") (pin "25") (pinfunction "25_25") (pintype "passive"))
      (node (ref "U2") (pin "3") (pinfunction "PE4/SERDES_TXN_3") (pintype "bidirectional"))
    )
    (net (code "84") (name "/PE5") (class "Default")
      (node (ref "P8") (pin "26") (pinfunction "26_26") (pintype "passive"))
      (node (ref "U2") (pin "4") (pinfunction "PE5/SERDES_RXP_4") (pintype "bidirectional"))
    )
    (net (code "85") (name "/PE6") (class "Default")
      (node (ref "P8") (pin "23") (pinfunction "23_23") (pintype "passive"))
      (node (ref "U2") (pin "5") (pinfunction "PE6/SERDES_RXN_5") (pintype "bidirectional"))
    )
    (net (code "86") (name "/PE7") (class "Default")
      (node (ref "P6") (pin "21") (pinfunction "21_21") (pintype "passive"))
      (node (ref "U2") (pin "52") (pinfunction "PE7/OP2_O0_52") (pintype "bidirectional"))
    )
    (net (code "87") (name "/PE8") (class "Default")
      (node (ref "P6") (pin "22") (pinfunction "22_22") (pintype "passive"))
      (node (ref "U2") (pin "53") (pinfunction "PE8/OP2_N0_53") (pintype "bidirectional"))
    )
    (net (code "88") (name "/PE9") (class "Default")
      (node (ref "P6") (pin "19") (pinfunction "19_19") (pintype "passive"))
      (node (ref "U2") (pin "54") (pinfunction "PE9/OP2_P0_54") (pintype "bidirectional"))
    )
    (net (code "89") (name "/PE10") (class "Default")
      (node (ref "P6") (pin "20") (pinfunction "20_20") (pintype "passive"))
      (node (ref "U2") (pin "55") (pinfunction "PE10_55") (pintype "bidirectional"))
    )
    (net (code "90") (name "/PE11") (class "Default")
      (node (ref "P6") (pin "17") (pinfunction "17_17") (pintype "passive"))
      (node (ref "U2") (pin "56") (pinfunction "PE11_56") (pintype "bidirectional"))
    )
    (net (code "91") (name "/PE12") (class "Default")
      (node (ref "P6") (pin "18") (pinfunction "18_18") (pintype "passive"))
      (node (ref "U2") (pin "57") (pinfunction "PE12_57") (pintype "bidirectional"))
    )
    (net (code "92") (name "/PE13") (class "Default")
      (node (ref "P6") (pin "15") (pinfunction "15_15") (pintype "passive"))
      (node (ref "U2") (pin "58") (pinfunction "PE13_58") (pintype "bidirectional"))
    )
    (net (code "93") (name "/PE14") (class "Default")
      (node (ref "P6") (pin "16") (pinfunction "16_16") (pintype "passive"))
      (node (ref "U2") (pin "59") (pinfunction "PE14_59") (pintype "bidirectional"))
    )
    (net (code "94") (name "/PE15") (class "Default")
      (node (ref "P6") (pin "13") (pinfunction "13_13") (pintype "passive"))
      (node (ref "U2") (pin "60") (pinfunction "PE15_60") (pintype "bidirectional"))
    )
    (net (code "95") (name "/PF0") (class "Default")
      (node (ref "P6") (pin "5") (pinfunction "5_5") (pintype "passive"))
      (node (ref "R23") (pin "1") (pintype "passive"))
      (node (ref "U2") (pin "77") (pinfunction "PF0_77") (pintype "bidirectional"))
    )
    (net (code "96") (name "/PF1") (class "Default")
      (node (ref "P6") (pin "6") (pinfunction "6_6") (pintype "passive"))
      (node (ref "U2") (pin "78") (pinfunction "PF1_78") (pintype "bidirectional"))
    )
    (net (code "97") (name "/PF2") (class "Default")
      (node (ref "P6") (pin "3") (pinfunction "3_3") (pintype "passive"))
      (node (ref "R24") (pin "1") (pintype "passive"))
      (node (ref "U2") (pin "79") (pinfunction "PF2_79") (pintype "bidirectional"))
    )
    (net (code "98") (name "/PF3") (class "Default")
      (node (ref "P5") (pin "13") (pinfunction "13_13") (pintype "passive"))
      (node (ref "U2") (pin "108") (pinfunction "PF3_108") (pintype "bidirectional"))
    )
    (net (code "99") (name "/PF4") (class "Default")
      (node (ref "P5") (pin "12") (pinfunction "12_12") (pintype "passive"))
      (node (ref "U2") (pin "109") (pinfunction "PF4_109") (pintype "bidirectional"))
    )
    (net (code "100") (name "/PF5") (class "Default")
      (node (ref "P5") (pin "11") (pinfunction "11_11") (pintype "passive"))
      (node (ref "U2") (pin "110") (pinfunction "PF5_110") (pintype "bidirectional"))
    )
    (net (code "101") (name "/PF6") (class "Default")
      (node (ref "P8") (pin "19") (pinfunction "19_19") (pintype "passive"))
      (node (ref "U2") (pin "17") (pinfunction "PF6_17") (pintype "bidirectional"))
    )
    (net (code "102") (name "/PF7") (class "Default")
      (node (ref "P8") (pin "20") (pinfunction "20_20") (pintype "passive"))
      (node (ref "U2") (pin "18") (pinfunction "PF7_18") (pintype "bidirectional"))
    )
    (net (code "103") (name "/PF8") (class "Default")
      (node (ref "P8") (pin "17") (pinfunction "17_17") (pintype "passive"))
      (node (ref "U2") (pin "19") (pinfunction "PF8/HSADC4_19") (pintype "bidirectional"))
    )
    (net (code "104") (name "/PF9") (class "Default")
      (node (ref "P8") (pin "18") (pinfunction "18_18") (pintype "passive"))
      (node (ref "U2") (pin "20") (pinfunction "PF9/HSADC5_20") (pintype "bidirectional"))
    )
    (net (code "105") (name "/PF10") (class "Default")
      (node (ref "P8") (pin "15") (pinfunction "15_15") (pintype "passive"))
      (node (ref "U2") (pin "21") (pinfunction "PF10/HSADC6_21") (pintype "bidirectional"))
    )
    (net (code "106") (name "/PF11") (class "Default")
      (node (ref "P6") (pin "26") (pinfunction "26_26") (pintype "passive"))
      (node (ref "U2") (pin "48") (pinfunction "PF11/OP2_P1_48") (pintype "bidirectional"))
    )
    (net (code "107") (name "/PF12") (class "Default")
      (node (ref "P6") (pin "23") (pinfunction "23_23") (pintype "passive"))
      (node (ref "U2") (pin "49") (pinfunction "PF12/OP2_N1_49") (pintype "bidirectional"))
    )
    (net (code "108") (name "/PF13") (class "Default")
      (node (ref "P6") (pin "24") (pinfunction "24_24") (pintype "passive"))
      (node (ref "U2") (pin "50") (pinfunction "PF13_50") (pintype "bidirectional"))
    )
    (net (code "109") (name "/PF14") (class "Default")
      (node (ref "P5") (pin "7") (pinfunction "7_7") (pintype "passive"))
      (node (ref "U2") (pin "113") (pinfunction "PF14_113") (pintype "bidirectional"))
    )
    (net (code "110") (name "/USBSS_RXN") (class "Default")
      (node (ref "P2") (pin "6") (pinfunction "SSRX+_6") (pintype "passive"))
      (node (ref "U2") (pin "126") (pinfunction "SSRXN_126") (pintype "bidirectional"))
    )
    (net (code "111") (name "/USBSS_RXP") (class "Default")
      (node (ref "P2") (pin "5") (pinfunction "SSRX-_5") (pintype "passive"))
      (node (ref "U2") (pin "127") (pinfunction "SSRXP_127") (pintype "bidirectional"))
    )
    (net (code "112") (name "/USBSS_TXN") (class "Default")
      (node (ref "C12") (pin "2") (pinfunction "2_2") (pintype "passive"))
      (node (ref "U2") (pin "123") (pinfunction "SSTXN_123") (pintype "bidirectional"))
    )
    (net (code "113") (name "/USBSS_TXP") (class "Default")
      (node (ref "C11") (pin "2") (pinfunction "2_2") (pintype "passive"))
      (node (ref "U2") (pin "124") (pinfunction "SSTXP_124") (pintype "bidirectional"))
    )
    (net (code "114") (name "/VBAT") (class "Default")
      (node (ref "C47") (pin "2") (pinfunction "2_2") (pintype "passive"))
      (node (ref "P9") (pin "11") (pinfunction "11_11") (pintype "passive"))
      (node (ref "U2") (pin "7") (pinfunction "VBAT_7") (pintype "bidirectional"))
    )
    (net (code "115") (name "/VDDK") (class "Default")
      (node (ref "C20") (pin "1") (pinfunction "1_1") (pintype "passive"))
      (node (ref "C45") (pin "2") (pinfunction "2_2") (pintype "passive"))
      (node (ref "C46") (pin "1") (pinfunction "1_1") (pintype "passive"))
      (node (ref "R26") (pin "1") (pintype "passive"))
      (node (ref "U2") (pin "11") (pinfunction "VDDK_11") (pintype "power_in"))
      (node (ref "U2") (pin "80") (pinfunction "VDDK_80") (pintype "power_in"))
    )
    (net (code "116") (name "/VDD_1.2A") (class "Default")
      (node (ref "C35") (pin "2") (pinfunction "2_2") (pintype "passive"))
      (node (ref "C36") (pin "2") (pinfunction "2_2") (pintype "passive"))
      (node (ref "R25") (pin "1") (pintype "passive"))
      (node (ref "U2") (pin "125") (pinfunction "VDD12A_125") (pintype "power_in"))
    )
    (net (code "117") (name "/VIO_1.8") (class "Default")
      (node (ref "C19") (pin "1") (pinfunction "1_1") (pintype "passive"))
      (node (ref "C27") (pin "1") (pinfunction "1_1") (pintype "passive"))
      (node (ref "C29") (pin "2") (pinfunction "2_2") (pintype "passive"))
      (node (ref "C30") (pin "1") (pinfunction "1_1") (pintype "passive"))
      (node (ref "P9") (pin "9") (pinfunction "9_9") (pintype "passive"))
      (node (ref "R11") (pin "1") (pintype "passive"))
      (node (ref "U2") (pin "105") (pinfunction "VIO18_105") (pintype "power_in"))
      (node (ref "U2") (pin "63") (pinfunction "VIO18_63") (pintype "power_in"))
      (node (ref "U2") (pin "81") (pinfunction "VIO18_81") (pintype "power_in"))
    )
    (net (code "118") (name "/X32KI") (class "Default")
      (node (ref "C22") (pin "1") (pinfunction "1_1") (pintype "passive"))
      (node (ref "R14") (pin "2") (pintype "passive"))
      (node (ref "U2") (pin "9") (pinfunction "PC14_9") (pintype "bidirectional"))
      (node (ref "Y1") (pin "1") (pinfunction "OSC1_1") (pintype "passive"))
    )
    (net (code "119") (name "/X32KO") (class "Default")
      (node (ref "C24") (pin "1") (pinfunction "1_1") (pintype "passive"))
      (node (ref "R15") (pin "2") (pintype "passive"))
      (node (ref "U2") (pin "10") (pinfunction "PC15_10") (pintype "bidirectional"))
      (node (ref "Y1") (pin "2") (pinfunction "OSC2_2") (pintype "passive"))
    )
    (net (code "120") (name "/XI") (class "Default")
      (node (ref "C23") (pin "2") (pinfunction "2_2") (pintype "passive"))
      (node (ref "U2") (pin "23") (pinfunction "XI_23") (pintype "bidirectional"))
      (node (ref "Y2") (pin "1") (pinfunction "OSC1_1") (pintype "passive"))
    )
    (net (code "121") (name "/XO") (class "Default")
      (node (ref "C25") (pin "2") (pinfunction "2_2") (pintype "passive"))
      (node (ref "R30") (pin "2") (pinfunction "2_2") (pintype "passive"))
      (node (ref "U2") (pin "24") (pinfunction "XO_24") (pintype "bidirectional"))
      (node (ref "Y2") (pin "3") (pinfunction "OSC2_3") (pintype "passive"))
    )
    (net (code "122") (name "1V2") (class "Default")
      (node (ref "C56") (pin "1") (pinfunction "1_1") (pintype "passive"))
      (node (ref "C57") (pin "2") (pinfunction "2_2") (pintype "passive"))
      (node (ref "L2") (pin "2") (pinfunction "2_2") (pintype "passive"))
      (node (ref "R25") (pin "2") (pintype "passive"))
      (node (ref "R26") (pin "2") (pintype "passive"))
      (node (ref "R27") (pin "1") (pintype "passive"))
    )
    (net (code "123") (name "3V3") (class "Default")
      (node (ref "C8") (pin "2") (pinfunction "2_2") (pintype "passive"))
      (node (ref "P3") (pin "1") (pinfunction "1_1") (pintype "passive"))
      (node (ref "P6") (pin "1") (pinfunction "1_1") (pintype "passive"))
      (node (ref "P6") (pin "2") (pinfunction "2_2") (pintype "passive"))
      (node (ref "P8") (pin "33") (pinfunction "33_33") (pintype "passive"))
      (node (ref "P8") (pin "34") (pinfunction "34_34") (pintype "passive"))
      (node (ref "P9") (pin "10") (pinfunction "10_10") (pintype "passive"))
      (node (ref "P9") (pin "12") (pinfunction "12_12") (pintype "passive"))
      (node (ref "P9") (pin "2") (pinfunction "2_2") (pintype "passive"))
      (node (ref "P9") (pin "4") (pinfunction "4_4") (pintype "passive"))
      (node (ref "P9") (pin "6") (pinfunction "6_6") (pintype "passive"))
      (node (ref "P9") (pin "8") (pinfunction "8_8") (pintype "passive"))
      (node (ref "R10") (pin "2") (pintype "passive"))
      (node (ref "R17") (pin "1") (pinfunction "1_1") (pintype "passive"))
      (node (ref "R2") (pin "2") (pintype "passive"))
      (node (ref "R5") (pin "2") (pintype "passive"))
      (node (ref "R7") (pin "2") (pintype "passive"))
      (node (ref "U3") (pin "5") (pinfunction "LDO_3V3_5") (pintype "power_in"))
    )
    (net (code "124") (name "5V") (class "Default")
      (node (ref "C17") (pin "2") (pinfunction "2_2") (pintype "passive"))
      (node (ref "C38") (pin "1") (pinfunction "1_1") (pintype "passive"))
      (node (ref "C4") (pin "1") (pinfunction "1_1") (pintype "passive"))
      (node (ref "C5") (pin "2") (pinfunction "2_2") (pintype "passive"))
      (node (ref "C53") (pin "2") (pinfunction "2_2") (pintype "passive"))
      (node (ref "C54") (pin "2") (pinfunction "2_2") (pintype "passive"))
      (node (ref "C58") (pin "1") (pinfunction "1_1") (pintype "passive"))
      (node (ref "L1") (pin "2") (pinfunction "2_2") (pintype "passive"))
      (node (ref "P10") (pin "2") (pinfunction "2_2") (pintype "passive"))
      (node (ref "P10") (pin "4") (pinfunction "4_4") (pintype "passive"))
      (node (ref "R3") (pin "2") (pintype "passive"))
      (node (ref "R45") (pin "1") (pintype "passive"))
      (node (ref "R46") (pin "1") (pintype "passive"))
      (node (ref "U3") (pin "4") (pinfunction "VIN5_4") (pintype "power_in"))
      (node (ref "U5") (pin "2") (pinfunction "VO-_2") (pintype "power_in"))
      (node (ref "U6") (pin "2") (pinfunction "VO-_2") (pintype "power_in"))
    )
    (net (code "125") (name "GND") (class "Default")
      (node (ref "C1") (pin "1") (pinfunction "1_1") (pintype "passive"))
      (node (ref "C16") (pin "2") (pinfunction "2_2") (pintype "passive"))
      (node (ref "C17") (pin "1") (pinfunction "1_1") (pintype "passive"))
      (node (ref "C18") (pin "2") (pinfunction "2_2") (pintype "passive"))
      (node (ref "C19") (pin "2") (pinfunction "2_2") (pintype "passive"))
      (node (ref "C2") (pin "1") (pinfunction "1_1") (pintype "passive"))
      (node (ref "C20") (pin "2") (pinfunction "2_2") (pintype "passive"))
      (node (ref "C22") (pin "2") (pinfunction "2_2") (pintype "passive"))
      (node (ref "C23") (pin "1") (pinfunction "1_1") (pintype "passive"))
      (node (ref "C24") (pin "2") (pinfunction "2_2") (pintype "passive"))
      (node (ref "C25") (pin "1") (pinfunction "1_1") (pintype "passive"))
      (node (ref "C26") (pin "2") (pinfunction "2_2") (pintype "passive"))
      (node (ref "C27") (pin "2") (pinfunction "2_2") (pintype "passive"))
      (node (ref "C29") (pin "1") (pinfunction "1_1") (pintype "passive"))
      (node (ref "C30") (pin "2") (pinfunction "2_2") (pintype "passive"))
      (node (ref "C31") (pin "1") (pinfunction "1_1") (pintype "passive"))
      (node (ref "C32") (pin "2") (pinfunction "2_2") (pintype "passive"))
      (node (ref "C33") (pin "1") (pinfunction "1_1") (pintype "passive"))
      (node (ref "C34") (pin "1") (pinfunction "1_1") (pintype "passive"))
      (node (ref "C35") (pin "1") (pinfunction "1_1") (pintype "passive"))
      (node (ref "C36") (pin "1") (pinfunction "1_1") (pintype "passive"))
      (node (ref "C37") (pin "1") (pinfunction "1_1") (pintype "passive"))
      (node (ref "C38") (pin "2") (pinfunction "2_2") (pintype "passive"))
      (node (ref "C39") (pin "1") (pinfunction "1_1") (pintype "passive"))
      (node (ref "C40") (pin "1") (pinfunction "1_1") (pintype "passive"))
      (node (ref "C41") (pin "1") (pinfunction "1_1") (pintype "passive"))
      (node (ref "C42") (pin "1") (pinfunction "1_1") (pintype "passive"))
      (node (ref "C43") (pin "1") (pinfunction "1_1") (pintype "passive"))
      (node (ref "C44") (pin "1") (pinfunction "1_1") (pintype "passive"))
      (node (ref "C45") (pin "1") (pinfunction "1_1") (pintype "passive"))
      (node (ref "C46") (pin "2") (pinfunction "2_2") (pintype "passive"))
      (node (ref "C47") (pin "1") (pinfunction "1_1") (pintype "passive"))
      (node (ref "C48") (pin "2") (pinfunction "2_2") (pintype "passive"))
      (node (ref "C49") (pin "1") (pinfunction "1_1") (pintype "passive"))
      (node (ref "C5") (pin "1") (pinfunction "1_1") (pintype "passive"))
      (node (ref "C51") (pin "1") (pinfunction "1_1") (pintype "passive"))
      (node (ref "C53") (pin "1") (pinfunction "1_1") (pintype "passive"))
      (node (ref "C54") (pin "1") (pinfunction "1_1") (pintype "passive"))
      (node (ref "C57") (pin "1") (pinfunction "1_1") (pintype "passive"))
      (node (ref "C58") (pin "2") (pinfunction "2_2") (pintype "passive"))
      (node (ref "C8") (pin "1") (pinfunction "1_1") (pintype "passive"))
      (node (ref "P1") (pin "A1") (pinfunction "GND_A1") (pintype "bidirectional"))
      (node (ref "P1") (pin "B1") (pinfunction "GND_B1") (pintype "bidirectional"))
      (node (ref "P10") (pin "5") (pinfunction "5_5") (pintype "passive"))
      (node (ref "P10") (pin "6") (pinfunction "6_6") (pintype "passive"))
      (node (ref "P2") (pin "0") (pinfunction "GND_0") (pintype "passive"))
      (node (ref "P2") (pin "4") (pinfunction "GND_4") (pintype "passive"))
      (node (ref "P2") (pin "7") (pinfunction "GND_7") (pintype "passive"))
      (node (ref "P3") (pin "2") (pinfunction "2_2") (pintype "passive"))
      (node (ref "P3") (pin "3") (pinfunction "3_3") (pintype "passive"))
      (node (ref "P3") (pin "4") (pinfunction "4_4") (pintype "passive"))
      (node (ref "P3") (pin "6") (pinfunction "6_6") (pintype "passive"))
      (node (ref "P3") (pin "8") (pinfunction "8_8") (pintype "passive"))
      (node (ref "P4") (pin "0") (pinfunction "GND_0") (pintype "power_in"))
      (node (ref "P4") (pin "4") (pinfunction "GND_4") (pintype "power_in"))
      (node (ref "P5") (pin "1") (pinfunction "1_1") (pintype "passive"))
      (node (ref "P6") (pin "4") (pinfunction "4_4") (pintype "passive"))
      (node (ref "P7") (pin "8") (pintype "passive"))
      (node (ref "P8") (pin "1") (pinfunction "1_1") (pintype "passive"))
      (node (ref "P8") (pin "31") (pinfunction "31_31") (pintype "passive"))
      (node (ref "P8") (pin "32") (pinfunction "32_32") (pintype "passive"))
      (node (ref "P9") (pin "13") (pinfunction "13_13") (pintype "passive"))
      (node (ref "P9") (pin "14") (pinfunction "14_14") (pintype "passive"))
      (node (ref "P9") (pin "16") (pinfunction "16_16") (pintype "passive"))
      (node (ref "P9") (pin "18") (pinfunction "18_18") (pintype "passive"))
      (node (ref "R12") (pin "2") (pinfunction "2_2") (pintype "passive"))
      (node (ref "R13") (pin "2") (pinfunction "2_2") (pintype "passive"))
      (node (ref "R28") (pin "2") (pintype "passive"))
      (node (ref "R30") (pin "1") (pinfunction "1_1") (pintype "passive"))
      (node (ref "R4") (pin "1") (pintype "passive"))
      (node (ref "S1") (pin "2") (pinfunction "2_2") (pintype "passive"))
      (node (ref "S2") (pin "2") (pinfunction "2_2") (pintype "passive"))
      (node (ref "U1") (pin "0") (pinfunction "GND_0") (pintype "power_in"))
      (node (ref "U1") (pin "5") (pinfunction "AGND_5") (pintype "power_in"))
      (node (ref "U2") (pin "0") (pinfunction "VSS_0") (pintype "power_in"))
      (node (ref "U2") (pin "122") (pinfunction "VSS_122") (pintype "power_in"))
      (node (ref "U2") (pin "22") (pinfunction "VSS_22") (pintype "power_in"))
      (node (ref "U2") (pin "31") (pinfunction "VSSA_31") (pintype "power_in"))
      (node (ref "U3") (pin "2") (pinfunction "GND_2") (pintype "power_in"))
      (node (ref "U5") (pin "1") (pinfunction "GND_1") (pintype "power_in"))
      (node (ref "U6") (pin "1") (pinfunction "GND_1") (pintype "power_in"))
    )
    (net (code "126") (name "Net-(C7-Pad2)") (class "Default")
      (node (ref "C7") (pin "2") (pinfunction "2_2") (pintype "passive"))
      (node (ref "L1") (pin "1") (pinfunction "1_1") (pintype "passive"))
      (node (ref "U1") (pin "7") (pinfunction "SW_7") (pintype "output"))
      (node (ref "U1") (pin "8") (pinfunction "SW_8") (pintype "output"))
    )
    (net (code "127") (name "Net-(C37-Pad2)") (class "Default")
      (node (ref "C37") (pin "2") (pinfunction "2_2") (pintype "passive"))
      (node (ref "P7") (pin "5") (pintype "passive"))
    )
    (net (code "128") (name "Net-(C39-Pad2)") (class "Default")
      (node (ref "C39") (pin "2") (pinfunction "2_2") (pintype "passive"))
      (node (ref "P7") (pin "4") (pintype "passive"))
    )
    (net (code "129") (name "Net-(LED1-A)") (class "Default")
      (node (ref "LED1") (pin "1") (pinfunction "A_1") (pintype "passive"))
      (node (ref "R16") (pin "2") (pintype "passive"))
    )
    (net (code "130") (name "Net-(LED2-A)") (class "Default")
      (node (ref "LED2") (pin "1") (pinfunction "A_1") (pintype "passive"))
      (node (ref "R18") (pin "2") (pintype "passive"))
    )
    (net (code "131") (name "Net-(P2-SSTX+)") (class "Default")
      (node (ref "C12") (pin "1") (pinfunction "1_1") (pintype "passive"))
      (node (ref "P2") (pin "9") (pinfunction "SSTX+_9") (pintype "passive"))
    )
    (net (code "132") (name "Net-(P2-SSTX-)") (class "Default")
      (node (ref "C11") (pin "1") (pinfunction "1_1") (pintype "passive"))
      (node (ref "P2") (pin "8") (pinfunction "SSTX-_8") (pintype "passive"))
    )
    (net (code "133") (name "Net-(P7-Pad9)") (class "Default")
      (node (ref "P7") (pin "9") (pintype "passive"))
      (node (ref "R21") (pin "2") (pintype "passive"))
    )
    (net (code "134") (name "Net-(P7-Pad12)") (class "Default")
      (node (ref "P7") (pin "12") (pintype "passive"))
      (node (ref "R22") (pin "2") (pintype "passive"))
    )
    (net (code "135") (name "Net-(U1-BST)") (class "Default")
      (node (ref "C7") (pin "1") (pinfunction "1_1") (pintype "passive"))
      (node (ref "U1") (pin "6") (pinfunction "BST_6") (pintype "power_in"))
    )
    (net (code "136") (name "Net-(U3-FB)") (class "Default")
      (node (ref "C56") (pin "2") (pinfunction "2_2") (pintype "passive"))
      (node (ref "R27") (pin "2") (pintype "passive"))
      (node (ref "R28") (pin "1") (pintype "passive"))
      (node (ref "U3") (pin "6") (pinfunction "FB_6") (pintype "input"))
    )
    (net (code "137") (name "Net-(U3-SW)") (class "Default")
      (node (ref "L2") (pin "1") (pinfunction "1_1") (pintype "passive"))
      (node (ref "U3") (pin "3") (pinfunction "SW_3") (pintype "output"))
    )
    (net (code "138") (name "VBUS_CC") (class "Default")
      (node (ref "C1") (pin "2") (pinfunction "2_2") (pintype "passive"))
      (node (ref "C2") (pin "2") (pinfunction "2_2") (pintype "passive"))
      (node (ref "P1") (pin "A4") (pinfunction "VBUS_A4") (pintype "bidirectional"))
      (node (ref "P1") (pin "B4") (pinfunction "VBUS_B4") (pintype "bidirectional"))
      (node (ref "P10") (pin "1") (pinfunction "1_1") (pintype "passive"))
      (node (ref "P10") (pin "3") (pinfunction "3_3") (pintype "passive"))
      (node (ref "P9") (pin "17") (pinfunction "17_17") (pintype "passive"))
      (node (ref "U1") (pin "1") (pinfunction "AVIN_1") (pintype "power_in"))
      (node (ref "U1") (pin "10") (pinfunction "VIN_10") (pintype "power_in"))
      (node (ref "U1") (pin "9") (pinfunction "VIN_9") (pintype "power_in"))
    )
    (net (code "139") (name "VBUS_FS") (class "Default")
      (node (ref "P4") (pin "1") (pinfunction "+5V_1") (pintype "power_in"))
      (node (ref "R46") (pin "2") (pintype "passive"))
      (node (ref "U6") (pin "3") (pinfunction "VI+_3") (pintype "power_in"))
    )
    (net (code "140") (name "VBUS_USB") (class "Default")
      (node (ref "P2") (pin "1") (pinfunction "VBUS_1") (pintype "passive"))
      (node (ref "P9") (pin "15") (pinfunction "15_15") (pintype "passive"))
      (node (ref "R45") (pin "2") (pintype "passive"))
      (node (ref "U5") (pin "3") (pinfunction "VI+_3") (pintype "power_in"))
    )
    (net (code "141") (name "VDD33") (class "Default")
      (node (ref "C16") (pin "1") (pinfunction "1_1") (pintype "passive"))
      (node (ref "C40") (pin "2") (pinfunction "2_2") (pintype "passive"))
      (node (ref "C41") (pin "2") (pinfunction "2_2") (pintype "passive"))
      (node (ref "C42") (pin "2") (pinfunction "2_2") (pintype "passive"))
      (node (ref "P9") (pin "5") (pinfunction "5_5") (pintype "passive"))
      (node (ref "R5") (pin "1") (pintype "passive"))
      (node (ref "U2") (pin "128") (pinfunction "VDD33_128") (pintype "power_in"))
      (node (ref "U2") (pin "16") (pinfunction "VDD33_16") (pintype "power_in"))
      (node (ref "U2") (pin "93") (pinfunction "VDD33_93") (pintype "power_in"))
    )
    (net (code "142") (name "VDD33A") (class "Default")
      (node (ref "C51") (pin "2") (pinfunction "2_2") (pintype "passive"))
      (node (ref "P9") (pin "3") (pinfunction "3_3") (pintype "passive"))
      (node (ref "R10") (pin "1") (pintype "passive"))
      (node (ref "U2") (pin "33") (pinfunction "VDD33A_33") (pintype "power_in"))
    )
    (net (code "143") (name "VDDIO") (class "Default")
      (node (ref "C18") (pin "1") (pinfunction "1_1") (pintype "passive"))
      (node (ref "C26") (pin "1") (pinfunction "1_1") (pintype "passive"))
      (node (ref "C32") (pin "1") (pinfunction "1_1") (pintype "passive"))
      (node (ref "C33") (pin "2") (pinfunction "2_2") (pintype "passive"))
      (node (ref "C34") (pin "2") (pinfunction "2_2") (pintype "passive"))
      (node (ref "C43") (pin "2") (pinfunction "2_2") (pintype "passive"))
      (node (ref "C44") (pin "2") (pinfunction "2_2") (pintype "passive"))
      (node (ref "C48") (pin "1") (pinfunction "1_1") (pintype "passive"))
      (node (ref "P9") (pin "7") (pinfunction "7_7") (pintype "passive"))
      (node (ref "R11") (pin "2") (pintype "passive"))
      (node (ref "R16") (pin "1") (pintype "passive"))
      (node (ref "R18") (pin "1") (pintype "passive"))
      (node (ref "R2") (pin "1") (pintype "passive"))
      (node (ref "R21") (pin "1") (pintype "passive"))
      (node (ref "R22") (pin "1") (pintype "passive"))
      (node (ref "U2") (pin "114") (pinfunction "VDDIO_114") (pintype "power_in"))
      (node (ref "U2") (pin "30") (pinfunction "VDDIO_30") (pintype "power_in"))
      (node (ref "U2") (pin "38") (pinfunction "VDDIO_38") (pintype "power_in"))
      (node (ref "U2") (pin "51") (pinfunction "VDDIO_51") (pintype "power_in"))
      (node (ref "U2") (pin "6") (pinfunction "VDDIO_6") (pintype "power_in"))
      (node (ref "U2") (pin "64") (pinfunction "VDDIO_64") (pintype "power_in"))
      (node (ref "U2") (pin "82") (pinfunction "VDDIO_82") (pintype "power_in"))
    )
    (net (code "144") (name "VREF") (class "Default")
      (node (ref "C49") (pin "2") (pinfunction "2_2") (pintype "passive"))
      (node (ref "P9") (pin "1") (pinfunction "1_1") (pintype "passive"))
      (node (ref "R7") (pin "1") (pintype "passive"))
      (node (ref "U2") (pin "32") (pinfunction "VREFP_32") (pintype "bidirectional"))
    )
    (net (code "145") (name "unconnected-(P1-RFU1-PadA8)") (class "Default")
      (node (ref "P1") (pin "A8") (pinfunction "RFU1_A8") (pintype "bidirectional+no_connect"))
    )
    (net (code "146") (name "unconnected-(P1-RFU1-PadB8)") (class "Default")
      (node (ref "P1") (pin "B8") (pinfunction "RFU1_B8") (pintype "bidirectional+no_connect"))
    )
    (net (code "147") (name "unconnected-(P7-Pad7)") (class "Default")
      (node (ref "P7") (pin "7") (pintype "passive"))
    )
    (net (code "148") (name "unconnected-(U1-NC.-Pad2)") (class "Default")
      (node (ref "U1") (pin "2") (pinfunction "NC._2") (pintype "passive"))
    )
    (net (code "149") (name "unconnected-(U1-NC.-Pad3)") (class "Default")
      (node (ref "U1") (pin "3") (pinfunction "NC._3") (pintype "passive"))
    )
    (net (code "150") (name "unconnected-(U3-NC.-Pad1)") (class "Default")
      (node (ref "U3") (pin "1") (pinfunction "NC._1") (pintype "passive+no_connect"))
    )
  )
)
